# Solar_Schematic.net
KiCad netlist of a schematic drawn in Altium Designer
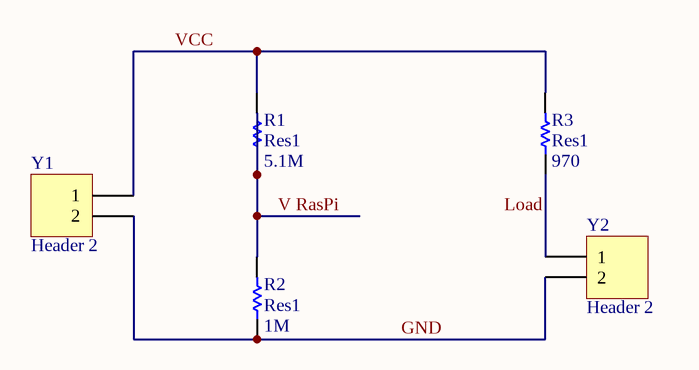
[diagram p0: Solar Schematic.SchDoc]

(export (version "E")
  (design (tool "Eeschema 10.0.6"))
  (components
    (comp (ref "R1")
      (value "Res1")
      (footprint "AXIAL-0.3")
      (description "Resistor")
      (fields (field (name "ALTIUM_VALUE") "5.1M") (field (name "PUBLISHER") "Altium Limited"))
      (libsource (lib "Miscellaneous Devices") (part "Res1"))
    )
    (comp (ref "R2")
      (value "Res1")
      (footprint "AXIAL-0.3")
      (description "Resistor")
      (fields (field (name "ALTIUM_VALUE") "1M") (field (name "PUBLISHER") "Altium Limited"))
      (libsource (lib "Miscellaneous Devices") (part "Res1"))
    )
    (comp (ref "R3")
      (value "Res1")
      (footprint "AXIAL-0.3")
      (description "Resistor")
      (fields (field (name "ALTIUM_VALUE") "970") (field (name "PUBLISHER") "Altium Limited"))
      (libsource (lib "Miscellaneous Devices") (part "Res1"))
    )
    (comp (ref "Y1")
      (value "Header 2")
      (footprint "HDR1X2")
      (description "Header, 2-Pin")
      (fields (field (name "PUBLISHER") "Altium Limited"))
      (libsource (lib "") (part "Header 2_1"))
    )
    (comp (ref "Y2")
      (value "Header 2")
      (footprint "HDR1X2")
      (description "Header, 2-Pin")
      (fields (field (name "PUBLISHER") "Altium Limited"))
      (libsource (lib "Miscellaneous Connectors") (part "Header 2"))
    )
  )
  (nets
    (net (code "1") (name "/GND") (class "Default")
      (node (ref "R2") (pin "1") (pinfunction "1_1") (pintype "passive"))
      (node (ref "Y1") (pin "2") (pinfunction "2_2") (pintype "passive"))
      (node (ref "Y2") (pin "2") (pinfunction "2_2") (pintype "passive"))
    )
    (net (code "3") (name "/V RasPi") (class "Default")
      (node (ref "R1") (pin "1") (pinfunction "1_1") (pintype "passive"))
      (node (ref "R2") (pin "2") (pinfunction "2_2") (pintype "passive"))
    )
    (net (code "4") (name "/VCC") (class "Default")
      (node (ref "R1") (pin "2") (pinfunction "2_2") (pintype "passive"))
      (node (ref "R3") (pin "2") (pinfunction "2_2") (pintype "passive"))
      (node (ref "Y1") (pin "1") (pinfunction "1_1") (pintype "passive"))
    )
    (net (code "5") (name "Net-(R3-Pad1)") (class "Default")
      (node (ref "R3") (pin "1") (pinfunction "1_1") (pintype "passive"))
      (node (ref "Y2") (pin "1") (pinfunction "1_1") (pintype "passive"))
    )
  )
)
